# Test_PCB.net
KiCad netlist of a schematic drawn in EAGLE
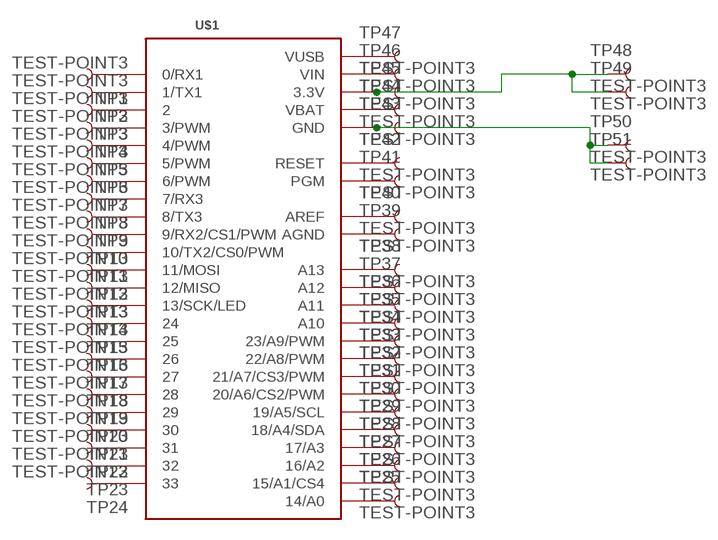
[diagram p0: schematic, sheet 1]

(export (version "E")
  (design (tool "Eeschema 10.0.6"))
  (components
    (comp (ref "TP1")
      (value "TEST-POINT3")
      (footprint "eagle-import:PAD.03X.03")
      (libsource (lib "eagle-import") (part "TEST-POINT3"))
    )
    (comp (ref "TP2")
      (value "TEST-POINT3")
      (footprint "eagle-import:PAD.03X.03")
      (libsource (lib "eagle-import") (part "TEST-POINT3"))
    )
    (comp (ref "TP3")
      (value "TEST-POINT3")
      (footprint "eagle-import:PAD.03X.03")
      (libsource (lib "eagle-import") (part "TEST-POINT3"))
    )
    (comp (ref "TP4")
      (value "TEST-POINT3")
      (footprint "eagle-import:PAD.03X.03")
      (libsource (lib "eagle-import") (part "TEST-POINT3"))
    )
    (comp (ref "TP5")
      (value "TEST-POINT3")
      (footprint "eagle-import:PAD.03X.03")
      (libsource (lib "eagle-import") (part "TEST-POINT3"))
    )
    (comp (ref "TP6")
      (value "TEST-POINT3")
      (footprint "eagle-import:PAD.03X.03")
      (libsource (lib "eagle-import") (part "TEST-POINT3"))
    )
    (comp (ref "TP7")
      (value "TEST-POINT3")
      (footprint "eagle-import:PAD.03X.03")
      (libsource (lib "eagle-import") (part "TEST-POINT3"))
    )
    (comp (ref "TP8")
      (value "TEST-POINT3")
      (footprint "eagle-import:PAD.03X.03")
      (libsource (lib "eagle-import") (part "TEST-POINT3"))
    )
    (comp (ref "TP9")
      (value "TEST-POINT3")
      (footprint "eagle-import:PAD.03X.03")
      (libsource (lib "eagle-import") (part "TEST-POINT3"))
    )
    (comp (ref "TP10")
      (value "TEST-POINT3")
      (footprint "eagle-import:PAD.03X.03")
      (libsource (lib "eagle-import") (part "TEST-POINT3"))
    )
    (comp (ref "TP11")
      (value "TEST-POINT3")
      (footprint "eagle-import:PAD.03X.03")
      (libsource (lib "eagle-import") (part "TEST-POINT3"))
    )
    (comp (ref "TP12")
      (value "TEST-POINT3")
      (footprint "eagle-import:PAD.03X.03")
      (libsource (lib "eagle-import") (part "TEST-POINT3"))
    )
    (comp (ref "TP13")
      (value "TEST-POINT3")
      (footprint "eagle-import:PAD.03X.03")
      (libsource (lib "eagle-import") (part "TEST-POINT3"))
    )
    (comp (ref "TP14")
      (value "TEST-POINT3")
      (footprint "eagle-import:PAD.03X.03")
      (libsource (lib "eagle-import") (part "TEST-POINT3"))
    )
    (comp (ref "TP15")
      (value "TEST-POINT3")
      (footprint "eagle-import:PAD.03X.03")
      (libsource (lib "eagle-import") (part "TEST-POINT3"))
    )
    (comp (ref "TP16")
      (value "TEST-POINT3")
      (footprint "eagle-import:PAD.03X.03")
      (libsource (lib "eagle-import") (part "TEST-POINT3"))
    )
    (comp (ref "TP17")
      (value "TEST-POINT3")
      (footprint "eagle-import:PAD.03X.03")
      (libsource (lib "eagle-import") (part "TEST-POINT3"))
    )
    (comp (ref "TP18")
      (value "TEST-POINT3")
      (footprint "eagle-import:PAD.03X.03")
      (libsource (lib "eagle-import") (part "TEST-POINT3"))
    )
    (comp (ref "TP19")
      (value "TEST-POINT3")
      (footprint "eagle-import:PAD.03X.03")
      (libsource (lib "eagle-import") (part "TEST-POINT3"))
    )
    (comp (ref "TP20")
      (value "TEST-POINT3")
      (footprint "eagle-import:PAD.03X.03")
      (libsource (lib "eagle-import") (part "TEST-POINT3"))
    )
    (comp (ref "TP21")
      (value "TEST-POINT3")
      (footprint "eagle-import:PAD.03X.03")
      (libsource (lib "eagle-import") (part "TEST-POINT3"))
    )
    (comp (ref "TP22")
      (value "TEST-POINT3")
      (footprint "eagle-import:PAD.03X.03")
      (libsource (lib "eagle-import") (part "TEST-POINT3"))
    )
    (comp (ref "TP23")
      (value "TEST-POINT3")
      (footprint "eagle-import:PAD.03X.03")
      (libsource (lib "eagle-import") (part "TEST-POINT3"))
    )
    (comp (ref "TP24")
      (value "TEST-POINT3")
      (footprint "eagle-import:PAD.03X.03")
      (libsource (lib "eagle-import") (part "TEST-POINT3"))
    )
    (comp (ref "TP25")
      (value "TEST-POINT3")
      (footprint "eagle-import:PAD.03X.03")
      (libsource (lib "eagle-import") (part "TEST-POINT3"))
    )
    (comp (ref "TP26")
      (value "TEST-POINT3")
      (footprint "eagle-import:PAD.03X.03")
      (libsource (lib "eagle-import") (part "TEST-POINT3"))
    )
    (comp (ref "TP27")
      (value "TEST-POINT3")
      (footprint "eagle-import:PAD.03X.03")
      (libsource (lib "eagle-import") (part "TEST-POINT3"))
    )
    (comp (ref "TP28")
      (value "TEST-POINT3")
      (footprint "eagle-import:PAD.03X.03")
      (libsource (lib "eagle-import") (part "TEST-POINT3"))
    )
    (comp (ref "TP29")
      (value "TEST-POINT3")
      (footprint "eagle-import:PAD.03X.03")
      (libsource (lib "eagle-import") (part "TEST-POINT3"))
    )
    (comp (ref "TP30")
      (value "TEST-POINT3")
      (footprint "eagle-import:PAD.03X.03")
      (libsource (lib "eagle-import") (part "TEST-POINT3"))
    )
    (comp (ref "TP31")
      (value "TEST-POINT3")
      (footprint "eagle-import:PAD.03X.03")
      (libsource (lib "eagle-import") (part "TEST-POINT3"))
    )
    (comp (ref "TP32")
      (value "TEST-POINT3")
      (footprint "eagle-import:PAD.03X.03")
      (libsource (lib "eagle-import") (part "TEST-POINT3"))
    )
    (comp (ref "TP33")
      (value "TEST-POINT3")
      (footprint "eagle-import:PAD.03X.03")
      (libsource (lib "eagle-import") (part "TEST-POINT3"))
    )
    (comp (ref "TP34")
      (value "TEST-POINT3")
      (footprint "eagle-import:PAD.03X.03")
      (libsource (lib "eagle-import") (part "TEST-POINT3"))
    )
    (comp (ref "TP35")
      (value "TEST-POINT3")
      (footprint "eagle-import:PAD.03X.03")
      (libsource (lib "eagle-import") (part "TEST-POINT3"))
    )
    (comp (ref "TP36")
      (value "TEST-POINT3")
      (footprint "eagle-import:PAD.03X.03")
      (libsource (lib "eagle-import") (part "TEST-POINT3"))
    )
    (comp (ref "TP37")
      (value "TEST-POINT3")
      (footprint "eagle-import:PAD.03X.03")
      (libsource (lib "eagle-import") (part "TEST-POINT3"))
    )
    (comp (ref "TP38")
      (value "TEST-POINT3")
      (footprint "eagle-import:PAD.03X.03")
      (libsource (lib "eagle-import") (part "TEST-POINT3"))
    )
    (comp (ref "TP39")
      (value "TEST-POINT3")
      (footprint "eagle-import:PAD.03X.03")
      (libsource (lib "eagle-import") (part "TEST-POINT3"))
    )
    (comp (ref "TP40")
      (value "TEST-POINT3")
      (footprint "eagle-import:PAD.03X.03")
      (libsource (lib "eagle-import") (part "TEST-POINT3"))
    )
    (comp (ref "TP41")
      (value "TEST-POINT3")
      (footprint "eagle-import:PAD.03X.03")
      (libsource (lib "eagle-import") (part "TEST-POINT3"))
    )
    (comp (ref "TP42")
      (value "TEST-POINT3")
      (footprint "eagle-import:PAD.03X.03")
      (libsource (lib "eagle-import") (part "TEST-POINT3"))
    )
    (comp (ref "TP43")
      (value "TEST-POINT3")
      (footprint "eagle-import:PAD.03X.03")
      (libsource (lib "eagle-import") (part "TEST-POINT3"))
    )
    (comp (ref "TP44")
      (value "TEST-POINT3")
      (footprint "eagle-import:PAD.03X.03")
      (libsource (lib "eagle-import") (part "TEST-POINT3"))
    )
    (comp (ref "TP45")
      (value "TEST-POINT3")
      (footprint "eagle-import:PAD.03X.03")
      (libsource (lib "eagle-import") (part "TEST-POINT3"))
    )
    (comp (ref "TP46")
      (value "TEST-POINT3")
      (footprint "eagle-import:PAD.03X.03")
      (libsource (lib "eagle-import") (part "TEST-POINT3"))
    )
    (comp (ref "TP47")
      (value "TEST-POINT3")
      (footprint "eagle-import:PAD.03X.03")
      (libsource (lib "eagle-import") (part "TEST-POINT3"))
    )
    (comp (ref "TP48")
      (value "TEST-POINT3")
      (footprint "eagle-import:PAD.03X.03")
      (libsource (lib "eagle-import") (part "TEST-POINT3"))
    )
    (comp (ref "TP49")
      (value "TEST-POINT3")
      (footprint "eagle-import:PAD.03X.03")
      (libsource (lib "eagle-import") (part "TEST-POINT3"))
    )
    (comp (ref "TP50")
      (value "TEST-POINT3")
      (footprint "eagle-import:PAD.03X.03")
      (libsource (lib "eagle-import") (part "TEST-POINT3"))
    )
    (comp (ref "TP51")
      (value "TEST-POINT3")
      (footprint "eagle-import:PAD.03X.03")
      (libsource (lib "eagle-import") (part "TEST-POINT3"))
    )
    (comp (ref "U$1")
      (value "TEENSY_3.0_ALLPINSTEENSY_3.0_ALLPINS-SMD")
      (footprint "eagle-import:TEENSY_3.0_ALLPINS-SMD")
      (libsource (lib "eagle-import") (part "TEENSY_3.0_ALLPINSTEENSY_3.0_ALLPINS-SMD"))
    )
  )
  (nets
    (net (code "1") (name "Net-(TP1-1)") (class "Default")
      (node (ref "TP1") (pin "P$1") (pinfunction "1_P$1") (pintype "bidirectional"))
      (node (ref "U$1") (pin "0") (pinfunction "0/RX1_0") (pintype "bidirectional"))
    )
    (net (code "2") (name "Net-(TP2-1)") (class "Default")
      (node (ref "TP2") (pin "P$1") (pinfunction "1_P$1") (pintype "bidirectional"))
      (node (ref "U$1") (pin "1") (pinfunction "1/TX1_1") (pintype "bidirectional"))
    )
    (net (code "3") (name "Net-(TP3-1)") (class "Default")
      (node (ref "TP3") (pin "P$1") (pinfunction "1_P$1") (pintype "bidirectional"))
      (node (ref "U$1") (pin "2") (pinfunction "2_2") (pintype "bidirectional"))
    )
    (net (code "4") (name "Net-(TP4-1)") (class "Default")
      (node (ref "TP4") (pin "P$1") (pinfunction "1_P$1") (pintype "bidirectional"))
      (node (ref "U$1") (pin "3") (pinfunction "3/PWM_3") (pintype "bidirectional"))
    )
    (net (code "5") (name "Net-(TP5-1)") (class "Default")
      (node (ref "TP5") (pin "P$1") (pinfunction "1_P$1") (pintype "bidirectional"))
      (node (ref "U$1") (pin "4") (pinfunction "4/PWM_4") (pintype "bidirectional"))
    )
    (net (code "6") (name "Net-(TP6-1)") (class "Default")
      (node (ref "TP6") (pin "P$1") (pinfunction "1_P$1") (pintype "bidirectional"))
      (node (ref "U$1") (pin "5") (pinfunction "5/PWM_5") (pintype "bidirectional"))
    )
    (net (code "7") (name "Net-(TP7-1)") (class "Default")
      (node (ref "TP7") (pin "P$1") (pinfunction "1_P$1") (pintype "bidirectional"))
      (node (ref "U$1") (pin "6") (pinfunction "6/PWM_6") (pintype "bidirectional"))
    )
    (net (code "8") (name "Net-(TP8-1)") (class "Default")
      (node (ref "TP8") (pin "P$1") (pinfunction "1_P$1") (pintype "bidirectional"))
      (node (ref "U$1") (pin "7") (pinfunction "7/RX3_7") (pintype "bidirectional"))
    )
    (net (code "9") (name "Net-(TP9-1)") (class "Default")
      (node (ref "TP9") (pin "P$1") (pinfunction "1_P$1") (pintype "bidirectional"))
      (node (ref "U$1") (pin "8") (pinfunction "8/TX3_8") (pintype "bidirectional"))
    )
    (net (code "10") (name "Net-(TP10-1)") (class "Default")
      (node (ref "TP10") (pin "P$1") (pinfunction "1_P$1") (pintype "bidirectional"))
      (node (ref "U$1") (pin "9") (pinfunction "9/RX2/CS1/PWM_9") (pintype "bidirectional"))
    )
    (net (code "11") (name "Net-(TP11-1)") (class "Default")
      (node (ref "TP11") (pin "P$1") (pinfunction "1_P$1") (pintype "bidirectional"))
      (node (ref "U$1") (pin "10") (pinfunction "10/TX2/CS0/PWM_10") (pintype "bidirectional"))
    )
    (net (code "12") (name "Net-(TP12-1)") (class "Default")
      (node (ref "TP12") (pin "P$1") (pinfunction "1_P$1") (pintype "bidirectional"))
      (node (ref "U$1") (pin "11") (pinfunction "11/MOSI_11") (pintype "bidirectional"))
    )
    (net (code "13") (name "Net-(TP13-1)") (class "Default")
      (node (ref "TP13") (pin "P$1") (pinfunction "1_P$1") (pintype "bidirectional"))
      (node (ref "U$1") (pin "12") (pinfunction "12/MISO_12") (pintype "bidirectional"))
    )
    (net (code "14") (name "Net-(TP14-1)") (class "Default")
      (node (ref "TP14") (pin "P$1") (pinfunction "1_P$1") (pintype "bidirectional"))
      (node (ref "U$1") (pin "13") (pinfunction "13/SCK/LED_13") (pintype "bidirectional"))
    )
    (net (code "15") (name "Net-(TP15-1)") (class "Default")
      (node (ref "TP15") (pin "P$1") (pinfunction "1_P$1") (pintype "bidirectional"))
      (node (ref "U$1") (pin "24") (pinfunction "24_24") (pintype "bidirectional"))
    )
    (net (code "16") (name "Net-(TP16-1)") (class "Default")
      (node (ref "TP16") (pin "P$1") (pinfunction "1_P$1") (pintype "bidirectional"))
      (node (ref "U$1") (pin "25") (pinfunction "25_25") (pintype "bidirectional"))
    )
    (net (code "17") (name "Net-(TP17-1)") (class "Default")
      (node (ref "TP17") (pin "P$1") (pinfunction "1_P$1") (pintype "bidirectional"))
      (node (ref "U$1") (pin "26") (pinfunction "26_26") (pintype "bidirectional"))
    )
    (net (code "18") (name "Net-(TP18-1)") (class "Default")
      (node (ref "TP18") (pin "P$1") (pinfunction "1_P$1") (pintype "bidirectional"))
      (node (ref "U$1") (pin "27") (pinfunction "27_27") (pintype "bidirectional"))
    )
    (net (code "19") (name "Net-(TP19-1)") (class "Default")
      (node (ref "TP19") (pin "P$1") (pinfunction "1_P$1") (pintype "bidirectional"))
      (node (ref "U$1") (pin "28") (pinfunction "28_28") (pintype "bidirectional"))
    )
    (net (code "20") (name "Net-(TP20-1)") (class "Default")
      (node (ref "TP20") (pin "P$1") (pinfunction "1_P$1") (pintype "bidirectional"))
      (node (ref "U$1") (pin "29") (pinfunction "29_29") (pintype "bidirectional"))
    )
    (net (code "21") (name "Net-(TP21-1)") (class "Default")
      (node (ref "TP21") (pin "P$1") (pinfunction "1_P$1") (pintype "bidirectional"))
      (node (ref "U$1") (pin "30") (pinfunction "30_30") (pintype "bidirectional"))
    )
    (net (code "22") (name "Net-(TP22-1)") (class "Default")
      (node (ref "TP22") (pin "P$1") (pinfunction "1_P$1") (pintype "bidirectional"))
      (node (ref "U$1") (pin "31") (pinfunction "31_31") (pintype "bidirectional"))
    )
    (net (code "23") (name "Net-(TP23-1)") (class "Default")
      (node (ref "TP23") (pin "P$1") (pinfunction "1_P$1") (pintype "bidirectional"))
      (node (ref "U$1") (pin "32") (pinfunction "32_32") (pintype "bidirectional"))
    )
    (net (code "24") (name "Net-(TP24-1)") (class "Default")
      (node (ref "TP24") (pin "P$1") (pinfunction "1_P$1") (pintype "bidirectional"))
      (node (ref "U$1") (pin "33") (pinfunction "33_33") (pintype "bidirectional"))
    )
    (net (code "25") (name "Net-(TP25-1)") (class "Default")
      (node (ref "TP25") (pin "P$1") (pinfunction "1_P$1") (pintype "bidirectional"))
      (node (ref "U$1") (pin "14/A0") (pinfunction "14/A0_14/A0") (pintype "bidirectional"))
    )
    (net (code "26") (name "Net-(TP26-1)") (class "Default")
      (node (ref "TP26") (pin "P$1") (pinfunction "1_P$1") (pintype "bidirectional"))
      (node (ref "U$1") (pin "15/A1") (pinfunction "15/A1/CS4_15/A1") (pintype "bidirectional"))
    )
    (net (code "27") (name "Net-(TP27-1)") (class "Default")
      (node (ref "TP27") (pin "P$1") (pinfunction "1_P$1") (pintype "bidirectional"))
      (node (ref "U$1") (pin "16/A2") (pinfunction "16/A2_16/A2") (pintype "bidirectional"))
    )
    (net (code "28") (name "Net-(TP28-1)") (class "Default")
      (node (ref "TP28") (pin "P$1") (pinfunction "1_P$1") (pintype "bidirectional"))
      (node (ref "U$1") (pin "17/A3") (pinfunction "17/A3_17/A3") (pintype "bidirectional"))
    )
    (net (code "29") (name "Net-(TP29-1)") (class "Default")
      (node (ref "TP29") (pin "P$1") (pinfunction "1_P$1") (pintype "bidirectional"))
      (node (ref "U$1") (pin "18/A4") (pinfunction "18/A4/SDA_18/A4") (pintype "bidirectional"))
    )
    (net (code "30") (name "Net-(TP30-1)") (class "Default")
      (node (ref "TP30") (pin "P$1") (pinfunction "1_P$1") (pintype "bidirectional"))
      (node (ref "U$1") (pin "19/A5") (pinfunction "19/A5/SCL_19/A5") (pintype "bidirectional"))
    )
    (net (code "31") (name "Net-(TP31-1)") (class "Default")
      (node (ref "TP31") (pin "P$1") (pinfunction "1_P$1") (pintype "bidirectional"))
      (node (ref "U$1") (pin "20/A6") (pinfunction "20/A6/CS2/PWM_20/A6") (pintype "bidirectional"))
    )
    (net (code "32") (name "Net-(TP32-1)") (class "Default")
      (node (ref "TP32") (pin "P$1") (pinfunction "1_P$1") (pintype "bidirectional"))
      (node (ref "U$1") (pin "21/A7") (pinfunction "21/A7/CS3/PWM_21/A7") (pintype "bidirectional"))
    )
    (net (code "33") (name "Net-(TP33-1)") (class "Default")
      (node (ref "TP33") (pin "P$1") (pinfunction "1_P$1") (pintype "bidirectional"))
      (node (ref "U$1") (pin "22/A8") (pinfunction "22/A8/PWM_22/A8") (pintype "bidirectional"))
    )
    (net (code "34") (name "Net-(TP34-1)") (class "Default")
      (node (ref "TP34") (pin "P$1") (pinfunction "1_P$1") (pintype "bidirectional"))
      (node (ref "U$1") (pin "23/A9") (pinfunction "23/A9/PWM_23/A9") (pintype "bidirectional"))
    )
    (net (code "35") (name "Net-(TP35-1)") (class "Default")
      (node (ref "TP35") (pin "P$1") (pinfunction "1_P$1") (pintype "bidirectional"))
      (node (ref "U$1") (pin "A10") (pinfunction "A10_A10") (pintype "bidirectional"))
    )
    (net (code "36") (name "Net-(TP36-1)") (class "Default")
      (node (ref "TP36") (pin "P$1") (pinfunction "1_P$1") (pintype "bidirectional"))
      (node (ref "U$1") (pin "A11") (pinfunction "A11_A11") (pintype "bidirectional"))
    )
    (net (code "37") (name "Net-(TP37-1)") (class "Default")
      (node (ref "TP37") (pin "P$1") (pinfunction "1_P$1") (pintype "bidirectional"))
      (node (ref "U$1") (pin "A12") (pinfunction "A12_A12") (pintype "bidirectional"))
    )
    (net (code "38") (name "Net-(TP38-1)") (class "Default")
      (node (ref "TP38") (pin "P$1") (pinfunction "1_P$1") (pintype "bidirectional"))
      (node (ref "U$1") (pin "A13") (pinfunction "A13_A13") (pintype "bidirectional"))
    )
    (net (code "39") (name "Net-(TP39-1)") (class "Default")
      (node (ref "TP39") (pin "P$1") (pinfunction "1_P$1") (pintype "bidirectional"))
      (node (ref "U$1") (pin "AGND") (pinfunction "AGND_AGND") (pintype "power_in"))
    )
    (net (code "40") (name "Net-(TP40-1)") (class "Default")
      (node (ref "TP40") (pin "P$1") (pinfunction "1_P$1") (pintype "bidirectional"))
      (node (ref "U$1") (pin "AREF") (pinfunction "AREF_AREF") (pintype "power_in"))
    )
    (net (code "41") (name "Net-(TP41-1)") (class "Default")
      (node (ref "TP41") (pin "P$1") (pinfunction "1_P$1") (pintype "bidirectional"))
      (node (ref "U$1") (pin "PGM") (pinfunction "PGM_PGM") (pintype "bidirectional"))
    )
    (net (code "42") (name "Net-(TP42-1)") (class "Default")
      (node (ref "TP42") (pin "P$1") (pinfunction "1_P$1") (pintype "bidirectional"))
      (node (ref "U$1") (pin "RESET") (pinfunction "RESET_RESET") (pintype "bidirectional"))
    )
    (net (code "43") (name "Net-(TP43-1)") (class "Default")
      (node (ref "TP43") (pin "P$1") (pinfunction "1_P$1") (pintype "bidirectional"))
      (node (ref "TP50") (pin "P$1") (pinfunction "1_P$1") (pintype "bidirectional"))
      (node (ref "TP51") (pin "P$1") (pinfunction "1_P$1") (pintype "bidirectional"))
      (node (ref "U$1") (pin "GND") (pinfunction "GND_GND") (pintype "power_in"))
      (node (ref "U$1") (pin "GND1") (pinfunction "GND_GND1") (pintype "power_in"))
      (node (ref "U$1") (pin "GND2") (pinfunction "GND_GND2") (pintype "power_in"))
    )
    (net (code "44") (name "Net-(TP44-1)") (class "Default")
      (node (ref "TP44") (pin "P$1") (pinfunction "1_P$1") (pintype "bidirectional"))
      (node (ref "U$1") (pin "VBAT") (pinfunction "VBAT_VBAT") (pintype "power_in"))
    )
    (net (code "45") (name "Net-(TP45-1)") (class "Default")
      (node (ref "TP45") (pin "P$1") (pinfunction "1_P$1") (pintype "bidirectional"))
      (node (ref "TP48") (pin "P$1") (pinfunction "1_P$1") (pintype "bidirectional"))
      (node (ref "TP49") (pin "P$1") (pinfunction "1_P$1") (pintype "bidirectional"))
      (node (ref "U$1") (pin "3.3V") (pinfunction "3.3V_3.3V") (pintype "power_in"))
      (node (ref "U$1") (pin "3.3V1") (pinfunction "3.3V_3.3V1") (pintype "power_in"))
      (node (ref "U$1") (pin "3.3V2") (pinfunction "3.3V_3.3V2") (pintype "power_in"))
    )
    (net (code "46") (name "Net-(TP46-1)") (class "Default")
      (node (ref "TP46") (pin "P$1") (pinfunction "1_P$1") (pintype "bidirectional"))
      (node (ref "U$1") (pin "VIN") (pinfunction "VIN_VIN") (pintype "power_in"))
    )
    (net (code "47") (name "Net-(TP47-1)") (class "Default")
      (node (ref "TP47") (pin "P$1") (pinfunction "1_P$1") (pintype "bidirectional"))
      (node (ref "U$1") (pin "VUSB") (pinfunction "VUSB_VUSB") (pintype "power_in"))
    )
  )
)
